# TIA.net
KiCad netlist of a schematic drawn in Altium Designer
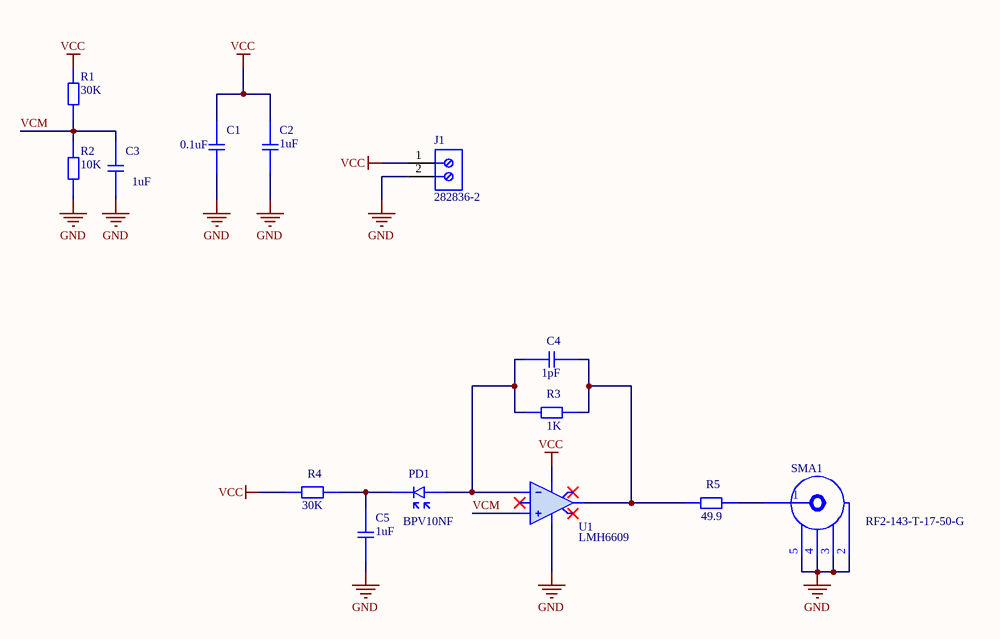
[diagram p0: TIA.SchDoc]

(export (version "E")
  (design (tool "Eeschema 10.0.6"))
  (components
    (comp (ref "C1")
      (value "0.1uF")
      (footprint "CAPC1608X90X35ML10T15")
      (libsource (lib "TIA_PARTS") (part "CAP0603"))
    )
    (comp (ref "C2")
      (value "1uF")
      (footprint "FP-CC0603-DB-IPC_B")
      (libsource (lib "TIA_PARTS") (part "CAP0603"))
    )
    (comp (ref "C3")
      (value "1uF")
      (footprint "FP-CC0603-DB-IPC_B")
      (libsource (lib "TIA_PARTS") (part "CAP0603"))
    )
    (comp (ref "C4")
      (value "1pF")
      (footprint "FP-C0603C-CF-IPC_B")
      (libsource (lib "TIA_PARTS") (part "CAP0603"))
    )
    (comp (ref "C5")
      (value "1uF")
      (footprint "FP-CC0603-DB-IPC_B")
      (libsource (lib "TIA_PARTS") (part "CAP0603"))
    )
    (comp (ref "J1")
      (value "282836-2")
      (footprint "TECO-282836-2_V")
      (description "Female Header, Pitch 5 mm, 1 x 2 Position, Height 10 mm, Tail Length 3.5 mm, Rohs, Bulk")
      (fields (field (name "VOLTAGE") "300V") (field (name "MANUFACTURER") "TE Connectivity"))
      (libsource (lib "Altium Content Vault") (part "CN-1P-F-TB2"))
    )
    (comp (ref "PD1")
      (value "BPV10NF")
      (footprint "FP-6_544-5185_02-4-MFG")
      (libsource (lib "TIA_PARTS") (part "BPV10NF"))
    )
    (comp (ref "R1")
      (value "30K")
      (footprint "FP-ERA3A-IPC_B")
      (libsource (lib "TIA_PARTS") (part "RES0603"))
    )
    (comp (ref "R2")
      (value "10K")
      (footprint "FP-AC0603-IPC_B")
      (libsource (lib "TIA_PARTS") (part "RES0603"))
    )
    (comp (ref "R3") (value "1K") (footprint "FP-ERA3A-IPC_B") (libsource (lib "TIA_PARTS") (part "RES0603")))
    (comp (ref "R4")
      (value "30K")
      (footprint "FP-ERA3A-IPC_B")
      (libsource (lib "TIA_PARTS") (part "RES0603"))
    )
    (comp (ref "R5")
      (value "49.9")
      (footprint "RESC1608X55X25ML10T15")
      (libsource (lib "TIA_PARTS") (part "RES0603"))
    )
    (comp (ref "SMA1")
      (value "RF2-143-T-17-50-G")
      (footprint "SMA_ADAM_TECH")
      (description "Conector:SMA;soclu;mamă;de margine;drept;SMT;pentruPCB;PTFE")
      (libsource (lib "SMA_CON") (part "RF2-143-T-17-50-G"))
    )
    (comp (ref "U1") (value "LMH6609") (footprint "D0008A_M") (libsource (lib "TIA_PARTS") (part "LMH6609")))
  )
  (nets
    (net (code "1") (name "/VCM") (class "Default")
      (node (ref "C3") (pin "2") (pinfunction "2_2") (pintype "passive"))
      (node (ref "R1") (pin "1") (pinfunction "1_1") (pintype "passive"))
      (node (ref "R2") (pin "2") (pinfunction "2_2") (pintype "passive"))
      (node (ref "U1") (pin "3") (pinfunction "INP_3") (pintype "passive"))
    )
    (net (code "2") (name "GND") (class "Default")
      (node (ref "C1") (pin "1") (pinfunction "1_1") (pintype "passive"))
      (node (ref "C2") (pin "1") (pinfunction "1_1") (pintype "passive"))
      (node (ref "C3") (pin "1") (pinfunction "1_1") (pintype "passive"))
      (node (ref "C5") (pin "1") (pinfunction "1_1") (pintype "passive"))
      (node (ref "J1") (pin "2") (pinfunction "2_2") (pintype "passive"))
      (node (ref "R2") (pin "1") (pinfunction "1_1") (pintype "passive"))
      (node (ref "SMA1") (pin "2") (pinfunction "GND_2") (pintype "passive"))
      (node (ref "SMA1") (pin "3") (pinfunction "GND_3") (pintype "passive"))
      (node (ref "SMA1") (pin "4") (pinfunction "GND_4") (pintype "passive"))
      (node (ref "SMA1") (pin "5") (pinfunction "GND_5") (pintype "passive"))
      (node (ref "U1") (pin "4") (pinfunction "VSN_4") (pintype "passive"))
    )
    (net (code "3") (name "Net-(PD1-Anode)") (class "Default")
      (node (ref "C5") (pin "2") (pinfunction "2_2") (pintype "passive"))
      (node (ref "PD1") (pin "1") (pinfunction "Anode_1") (pintype "passive"))
      (node (ref "R4") (pin "2") (pinfunction "2_2") (pintype "passive"))
    )
    (net (code "4") (name "Net-(PD1-Cathode)") (class "Default")
      (node (ref "C4") (pin "1") (pinfunction "1_1") (pintype "passive"))
      (node (ref "PD1") (pin "2") (pinfunction "Cathode_2") (pintype "passive"))
      (node (ref "R3") (pin "1") (pinfunction "1_1") (pintype "passive"))
      (node (ref "U1") (pin "2") (pinfunction "INN_2") (pintype "passive"))
    )
    (net (code "5") (name "Net-(SMA1-COAX)") (class "Default")
      (node (ref "R5") (pin "2") (pinfunction "2_2") (pintype "passive"))
      (node (ref "SMA1") (pin "1") (pinfunction "COAX_1") (pintype "passive"))
    )
    (net (code "6") (name "Net-(U1-OUT)") (class "Default")
      (node (ref "C4") (pin "2") (pinfunction "2_2") (pintype "passive"))
      (node (ref "R3") (pin "2") (pinfunction "2_2") (pintype "passive"))
      (node (ref "R5") (pin "1") (pinfunction "1_1") (pintype "passive"))
      (node (ref "U1") (pin "6") (pinfunction "OUT_6") (pintype "passive"))
    )
    (net (code "7") (name "VCC") (class "Default")
      (node (ref "C1") (pin "2") (pinfunction "2_2") (pintype "passive"))
      (node (ref "C2") (pin "2") (pinfunction "2_2") (pintype "passive"))
      (node (ref "J1") (pin "1") (pinfunction "1_1") (pintype "passive"))
      (node (ref "R1") (pin "2") (pinfunction "2_2") (pintype "passive"))
      (node (ref "R4") (pin "1") (pinfunction "1_1") (pintype "passive"))
      (node (ref "U1") (pin "7") (pinfunction "VSP_7") (pintype "passive"))
    )
    (net (code "8") (name "unconnected-(U1-N{slash}C-Pad1)") (class "Default")
      (node (ref "U1") (pin "1") (pinfunction "N/C_1") (pintype "passive+no_connect"))
    )
    (net (code "9") (name "unconnected-(U1-N{slash}C-Pad5)") (class "Default")
      (node (ref "U1") (pin "5") (pinfunction "N/C_5") (pintype "passive+no_connect"))
    )
    (net (code "10") (name "unconnected-(U1-N{slash}C-Pad8)") (class "Default")
      (node (ref "U1") (pin "8") (pinfunction "N/C_8") (pintype "passive+no_connect"))
    )
  )
)
